# Gate_Protection.net
KiCad netlist of a schematic drawn in Altium Designer
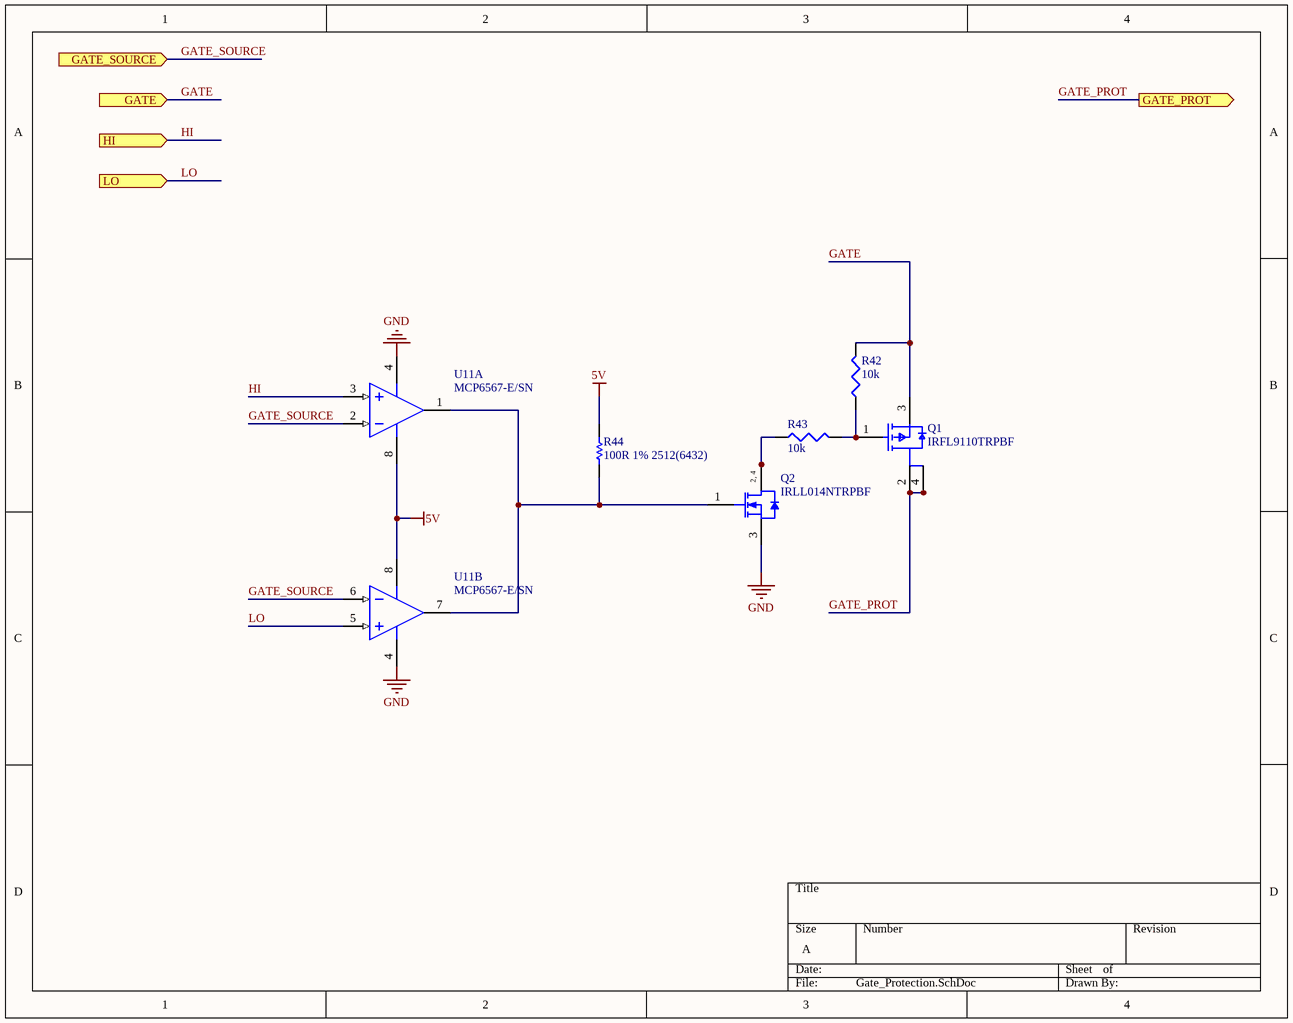
[diagram p0: Gate_Protection.SchDoc]

(export (version "E")
  (design (tool "Eeschema 10.0.6"))
  (components
    (comp (ref "Q1")
      (value "IRFL9110TRPBF")
      (footprint "FP-S-82109-IPC_C")
      (description "MOSFET P-CH 100V 1.1A SOT223")
      (fields
        (field (name "MANUFACTURER") "Vishay")
        (field (name "OCTOPART") "https://octopart.com/irfl9110trpbf-vishay-39554730")
      )
      (libsource (lib "Altium Content Vault") (part "e20c127729a63890b18c4f92231bf5d"))
    )
    (comp (ref "Q2")
      (value "IRLL014NTRPBF")
      (footprint "ONSC-SOT-223-4-318E-04_V")
      (description "Mosfet, Power; N-ch; Vdss 55V; Rds(on) 0.14 Ohm; Id 2.8A; SOT-223; Pd 2.1W; Vgs +/-16V")
      (fields (field (name "PARTNUMBER") "NVF3055L108T1G") (field (name "MANUFACTURER") "On Semiconductor"))
      (libsource (lib "Altium Content Vault") (part "ONSC-NMOS-G1D2S3D4-4"))
    )
    (comp (ref "R42")
      (value "10k")
      (footprint "J1-0603")
      (description "Resistor")
      (fields (field (name "PUBLISHER") "Altium Limited"))
      (libsource (lib "Miscellaneous Devices") (part "Res3"))
    )
    (comp (ref "R43")
      (value "10k")
      (footprint "J1-0603")
      (description "Resistor")
      (fields (field (name "PUBLISHER") "Altium Limited"))
      (libsource (lib "Miscellaneous Devices") (part "Res3"))
    )
    (comp (ref "R44")
      (value "100R 1% 2512(6432)")
      (footprint "RESC2512(6432)_N")
      (description "100R 1W 1% 2512 (6432 Metric)  SMD")
      (fields (field (name "POWER") "1 W") (field (name "TOLERANCE") "1 %"))
      (libsource (lib "Altium Content Vault") (part "RES"))
    )
    (comp (ref "U11")
      (value "MCP6567-E/SN")
      (footprint "SOIC-SN8_L")
      (description "None")
      (libsource (lib "Altium Content Vault") (part "LO-COMP-MCP6567-IL8-OC"))
    )
  )
  (nets
    (net (code "1") (name "/GATE") (class "Default")
      (node (ref "Q1") (pin "3") (pinfunction "S_3") (pintype "passive"))
      (node (ref "R42") (pin "2") (pinfunction "2_2") (pintype "passive"))
    )
    (net (code "2") (name "/GATE_PROT") (class "Default")
      (node (ref "Q1") (pin "2") (pinfunction "D_2") (pintype "passive"))
      (node (ref "Q1") (pin "4") (pinfunction "D_4") (pintype "passive"))
    )
    (net (code "3") (name "/GATE_SOURCE") (class "Default")
      (node (ref "U11") (pin "2") (pinfunction "INA-_2") (pintype "input"))
      (node (ref "U11") (pin "6") (pinfunction "INB-_6") (pintype "input"))
    )
    (net (code "4") (name "/HI") (class "Default")
      (node (ref "U11") (pin "3") (pinfunction "INA+_3") (pintype "input"))
    )
    (net (code "5") (name "/LO") (class "Default")
      (node (ref "U11") (pin "5") (pinfunction "INB+_5") (pintype "input"))
    )
    (net (code "6") (name "5V") (class "Default")
      (node (ref "R44") (pin "2") (pinfunction "2_2") (pintype "passive"))
      (node (ref "U11") (pin "8") (pinfunction "VDD_8") (pintype "power_in"))
    )
    (net (code "7") (name "GND") (class "Default")
      (node (ref "Q2") (pin "3") (pinfunction "S_3") (pintype "passive"))
      (node (ref "U11") (pin "4") (pinfunction "VSS_4") (pintype "power_in"))
    )
    (net (code "8") (name "Net-(Q1-G)") (class "Default")
      (node (ref "Q1") (pin "1") (pinfunction "G_1") (pintype "passive"))
      (node (ref "R42") (pin "1") (pinfunction "1_1") (pintype "passive"))
      (node (ref "R43") (pin "2") (pinfunction "2_2") (pintype "passive"))
    )
    (net (code "9") (name "Net-(Q2-D-Pad2)") (class "Default")
      (node (ref "Q2") (pin "2") (pinfunction "D_2") (pintype "passive"))
      (node (ref "Q2") (pin "4") (pinfunction "D_4") (pintype "passive"))
      (node (ref "R43") (pin "1") (pinfunction "1_1") (pintype "passive"))
    )
    (net (code "10") (name "Net-(Q2-G)") (class "Default")
      (node (ref "Q2") (pin "1") (pinfunction "G_1") (pintype "passive"))
      (node (ref "R44") (pin "1") (pinfunction "1_1") (pintype "passive"))
      (node (ref "U11") (pin "1") (pinfunction "OUTA_1") (pintype "open_collector"))
      (node (ref "U11") (pin "7") (pinfunction "OUTB_7") (pintype "open_collector"))
    )
  )
)
